# MIDI-Patchbay-Display.net
KiCad netlist of a schematic drawn in EAGLE
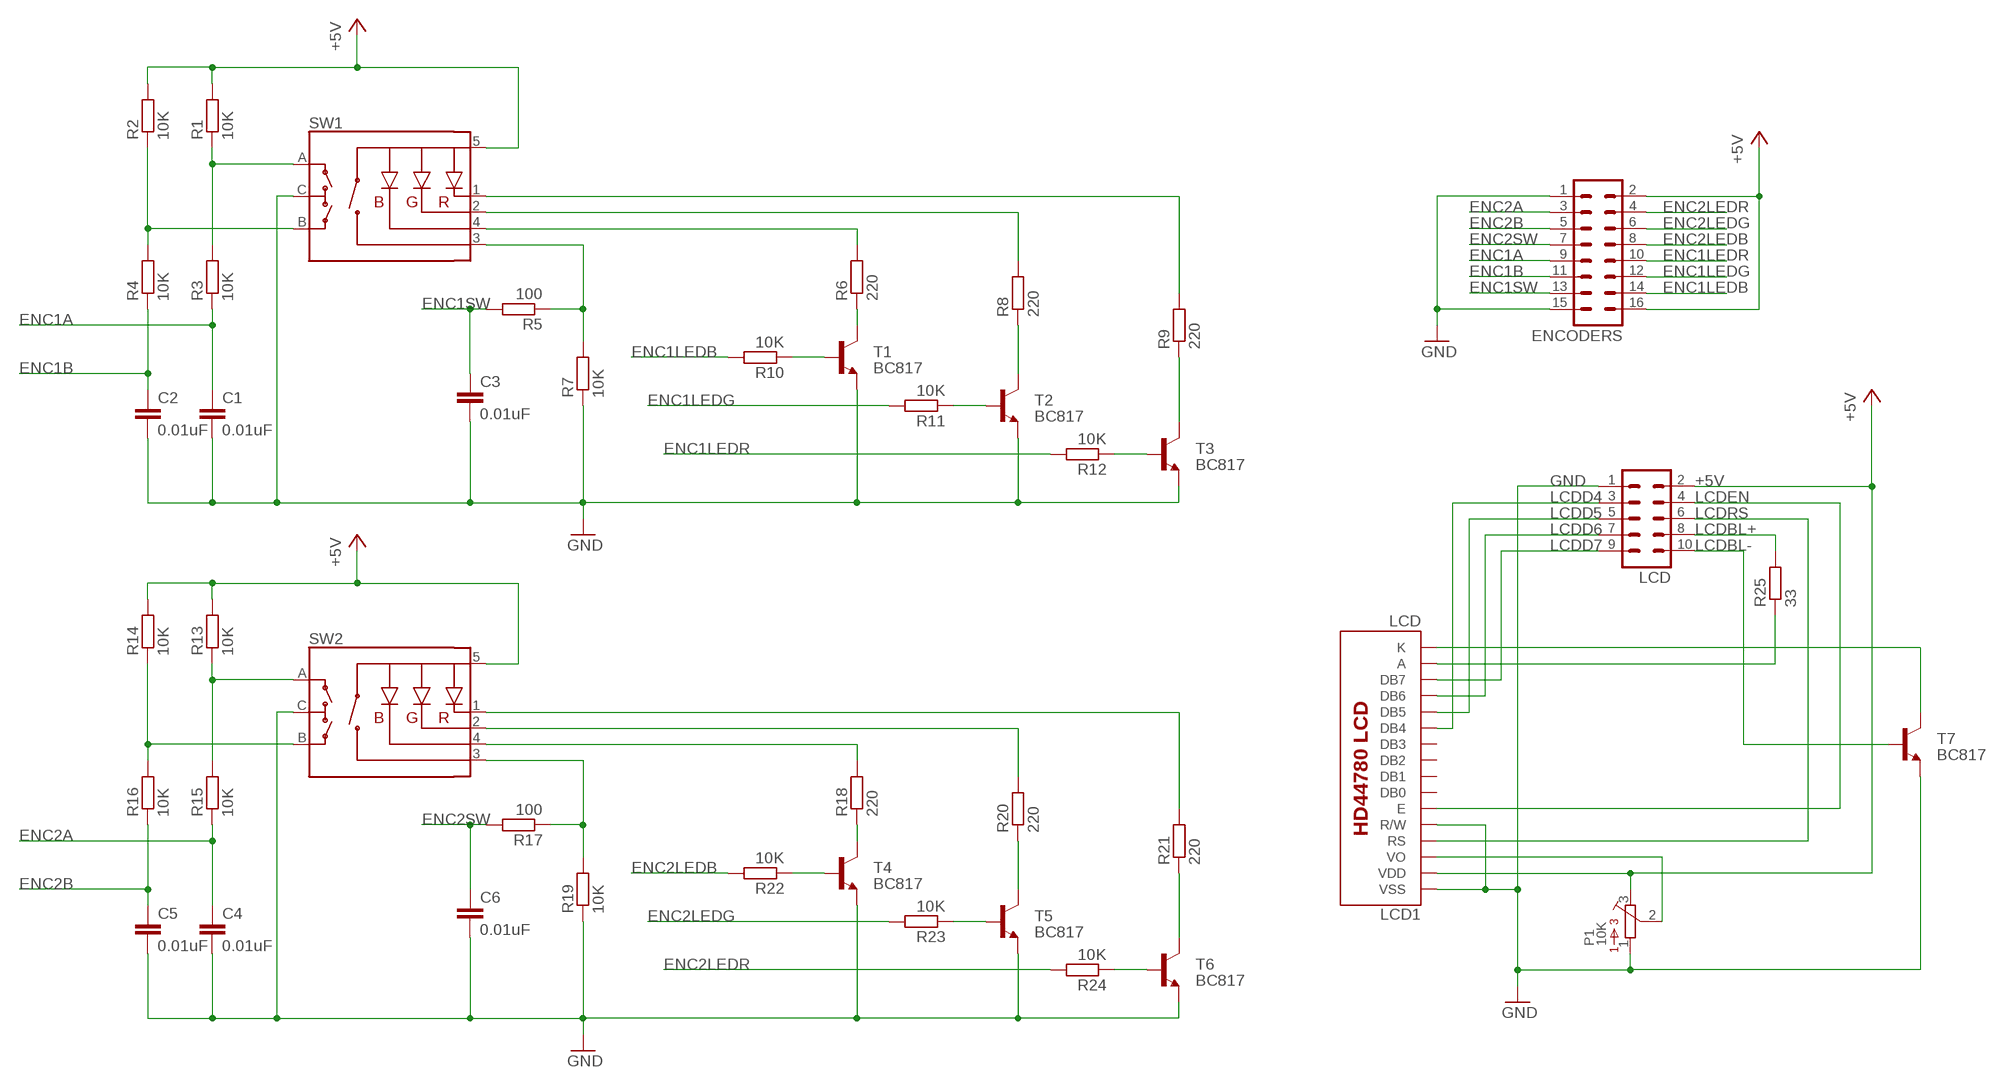
[diagram p0: schematic, sheet 1]

(export (version "E")
  (design (tool "Eeschema 10.0.6"))
  (components
    (comp (ref "C1")
      (value "0.01uF")
      (footprint "eagle-import:0805")
      (libsource (lib "eagle-import") (part "CAPACITOR"))
    )
    (comp (ref "C2")
      (value "0.01uF")
      (footprint "eagle-import:0805")
      (libsource (lib "eagle-import") (part "CAPACITOR"))
    )
    (comp (ref "C3")
      (value "0.01uF")
      (footprint "eagle-import:0805")
      (libsource (lib "eagle-import") (part "CAPACITOR"))
    )
    (comp (ref "C4")
      (value "0.01uF")
      (footprint "eagle-import:0805")
      (libsource (lib "eagle-import") (part "CAPACITOR"))
    )
    (comp (ref "C5")
      (value "0.01uF")
      (footprint "eagle-import:0805")
      (libsource (lib "eagle-import") (part "CAPACITOR"))
    )
    (comp (ref "C6")
      (value "0.01uF")
      (footprint "eagle-import:0805")
      (libsource (lib "eagle-import") (part "CAPACITOR"))
    )
    (comp (ref "ENCODERS")
      (value "ML16")
      (footprint "eagle-import:ML16")
      (libsource (lib "eagle-import") (part "ML16"))
    )
    (comp (ref "LCD")
      (value "ML10")
      (footprint "eagle-import:ML10")
      (libsource (lib "eagle-import") (part "ML10"))
    )
    (comp (ref "LCD1")
      (value "LCD")
      (footprint "eagle-import:LCD-16X2-4HOLES")
      (libsource (lib "eagle-import") (part "LCD-HD4478016X2-4-HOLES4-HOLES"))
    )
    (comp (ref "P1")
      (value "10K")
      (footprint "eagle-import:3386W")
      (libsource (lib "eagle-import") (part "3296W_TRIM_POT"))
    )
    (comp (ref "R1")
      (value "10K")
      (footprint "eagle-import:R0805")
      (libsource (lib "eagle-import") (part "RESISTORR0805"))
    )
    (comp (ref "R2")
      (value "10K")
      (footprint "eagle-import:R0805")
      (libsource (lib "eagle-import") (part "RESISTORR0805"))
    )
    (comp (ref "R3")
      (value "10K")
      (footprint "eagle-import:R0805")
      (libsource (lib "eagle-import") (part "RESISTORR0805"))
    )
    (comp (ref "R4")
      (value "10K")
      (footprint "eagle-import:R0805")
      (libsource (lib "eagle-import") (part "RESISTORR0805"))
    )
    (comp (ref "R5")
      (value "100")
      (footprint "eagle-import:R0805")
      (libsource (lib "eagle-import") (part "RESISTORR0805"))
    )
    (comp (ref "R6")
      (value "220")
      (footprint "eagle-import:R0805")
      (libsource (lib "eagle-import") (part "RESISTORR0805"))
    )
    (comp (ref "R7")
      (value "10K")
      (footprint "eagle-import:R0805")
      (libsource (lib "eagle-import") (part "RESISTORR0805"))
    )
    (comp (ref "R8")
      (value "220")
      (footprint "eagle-import:R0805")
      (libsource (lib "eagle-import") (part "RESISTORR0805"))
    )
    (comp (ref "R9")
      (value "220")
      (footprint "eagle-import:R0805")
      (libsource (lib "eagle-import") (part "RESISTORR0805"))
    )
    (comp (ref "R10")
      (value "10K")
      (footprint "eagle-import:R0805")
      (libsource (lib "eagle-import") (part "RESISTORR0805"))
    )
    (comp (ref "R11")
      (value "10K")
      (footprint "eagle-import:R0805")
      (libsource (lib "eagle-import") (part "RESISTORR0805"))
    )
    (comp (ref "R12")
      (value "10K")
      (footprint "eagle-import:R0805")
      (libsource (lib "eagle-import") (part "RESISTORR0805"))
    )
    (comp (ref "R13")
      (value "10K")
      (footprint "eagle-import:R0805")
      (libsource (lib "eagle-import") (part "RESISTORR0805"))
    )
    (comp (ref "R14")
      (value "10K")
      (footprint "eagle-import:R0805")
      (libsource (lib "eagle-import") (part "RESISTORR0805"))
    )
    (comp (ref "R15")
      (value "10K")
      (footprint "eagle-import:R0805")
      (libsource (lib "eagle-import") (part "RESISTORR0805"))
    )
    (comp (ref "R16")
      (value "10K")
      (footprint "eagle-import:R0805")
      (libsource (lib "eagle-import") (part "RESISTORR0805"))
    )
    (comp (ref "R17")
      (value "100")
      (footprint "eagle-import:R0805")
      (libsource (lib "eagle-import") (part "RESISTORR0805"))
    )
    (comp (ref "R18")
      (value "220")
      (footprint "eagle-import:R0805")
      (libsource (lib "eagle-import") (part "RESISTORR0805"))
    )
    (comp (ref "R19")
      (value "10K")
      (footprint "eagle-import:R0805")
      (libsource (lib "eagle-import") (part "RESISTORR0805"))
    )
    (comp (ref "R20")
      (value "220")
      (footprint "eagle-import:R0805")
      (libsource (lib "eagle-import") (part "RESISTORR0805"))
    )
    (comp (ref "R21")
      (value "220")
      (footprint "eagle-import:R0805")
      (libsource (lib "eagle-import") (part "RESISTORR0805"))
    )
    (comp (ref "R22")
      (value "10K")
      (footprint "eagle-import:R0805")
      (libsource (lib "eagle-import") (part "RESISTORR0805"))
    )
    (comp (ref "R23")
      (value "10K")
      (footprint "eagle-import:R0805")
      (libsource (lib "eagle-import") (part "RESISTORR0805"))
    )
    (comp (ref "R24")
      (value "10K")
      (footprint "eagle-import:R0805")
      (libsource (lib "eagle-import") (part "RESISTORR0805"))
    )
    (comp (ref "R25")
      (value "33")
      (footprint "eagle-import:R0805")
      (libsource (lib "eagle-import") (part "RESISTORR0805"))
    )
    (comp (ref "SW1")
      (value "ENCODER_RGB_CA")
      (footprint "eagle-import:ENCODER_LED_3")
      (libsource (lib "eagle-import") (part "ENCODER_RGB_CA"))
    )
    (comp (ref "SW2")
      (value "ENCODER_RGB_CA")
      (footprint "eagle-import:ENCODER_LED_3")
      (libsource (lib "eagle-import") (part "ENCODER_RGB_CA"))
    )
    (comp (ref "T1")
      (value "BC817")
      (footprint "eagle-import:SOT23")
      (libsource (lib "eagle-import") (part "BC817"))
    )
    (comp (ref "T2")
      (value "BC817")
      (footprint "eagle-import:SOT23")
      (libsource (lib "eagle-import") (part "BC817"))
    )
    (comp (ref "T3")
      (value "BC817")
      (footprint "eagle-import:SOT23")
      (libsource (lib "eagle-import") (part "BC817"))
    )
    (comp (ref "T4")
      (value "BC817")
      (footprint "eagle-import:SOT23")
      (libsource (lib "eagle-import") (part "BC817"))
    )
    (comp (ref "T5")
      (value "BC817")
      (footprint "eagle-import:SOT23")
      (libsource (lib "eagle-import") (part "BC817"))
    )
    (comp (ref "T6")
      (value "BC817")
      (footprint "eagle-import:SOT23")
      (libsource (lib "eagle-import") (part "BC817"))
    )
    (comp (ref "T7")
      (value "BC817")
      (footprint "eagle-import:SOT23")
      (libsource (lib "eagle-import") (part "BC817"))
    )
  )
  (nets
    (net (code "1") (name "+5V") (class "Default")
      (node (ref "ENCODERS") (pin "16") (pinfunction "16_16") (pintype "passive"))
      (node (ref "ENCODERS") (pin "2") (pinfunction "2_2") (pintype "passive"))
      (node (ref "LCD") (pin "2") (pinfunction "2_2") (pintype "passive"))
      (node (ref "LCD1") (pin "2") (pinfunction "VDD_2") (pintype "power_in"))
      (node (ref "P1") (pin "3") (pinfunction "3_3") (pintype "passive"))
      (node (ref "R1") (pin "2") (pinfunction "2_2") (pintype "passive"))
      (node (ref "R13") (pin "2") (pinfunction "2_2") (pintype "passive"))
      (node (ref "R14") (pin "2") (pinfunction "2_2") (pintype "passive"))
      (node (ref "R2") (pin "2") (pinfunction "2_2") (pintype "passive"))
      (node (ref "SW1") (pin "5") (pinfunction "+_5") (pintype "passive"))
      (node (ref "SW2") (pin "5") (pinfunction "+_5") (pintype "passive"))
    )
    (net (code "2") (name "/ENC1A") (class "Default")
      (node (ref "C1") (pin "1") (pinfunction "1_1") (pintype "passive"))
      (node (ref "ENCODERS") (pin "9") (pinfunction "9_9") (pintype "passive"))
      (node (ref "R3") (pin "1") (pinfunction "1_1") (pintype "passive"))
    )
    (net (code "3") (name "/ENC1B") (class "Default")
      (node (ref "C2") (pin "1") (pinfunction "1_1") (pintype "passive"))
      (node (ref "ENCODERS") (pin "11") (pinfunction "11_11") (pintype "passive"))
      (node (ref "R4") (pin "1") (pinfunction "1_1") (pintype "passive"))
    )
    (net (code "4") (name "/ENC1LEDB") (class "Default")
      (node (ref "ENCODERS") (pin "14") (pinfunction "14_14") (pintype "passive"))
      (node (ref "R10") (pin "2") (pinfunction "2_2") (pintype "passive"))
    )
    (net (code "5") (name "/ENC1LEDG") (class "Default")
      (node (ref "ENCODERS") (pin "12") (pinfunction "12_12") (pintype "passive"))
      (node (ref "R11") (pin "2") (pinfunction "2_2") (pintype "passive"))
    )
    (net (code "6") (name "/ENC1LEDR") (class "Default")
      (node (ref "ENCODERS") (pin "10") (pinfunction "10_10") (pintype "passive"))
      (node (ref "R12") (pin "2") (pinfunction "2_2") (pintype "passive"))
    )
    (net (code "7") (name "/ENC1SW") (class "Default")
      (node (ref "C3") (pin "1") (pinfunction "1_1") (pintype "passive"))
      (node (ref "ENCODERS") (pin "13") (pinfunction "13_13") (pintype "passive"))
      (node (ref "R5") (pin "2") (pinfunction "2_2") (pintype "passive"))
    )
    (net (code "8") (name "/ENC2A") (class "Default")
      (node (ref "C4") (pin "1") (pinfunction "1_1") (pintype "passive"))
      (node (ref "ENCODERS") (pin "3") (pinfunction "3_3") (pintype "passive"))
      (node (ref "R15") (pin "1") (pinfunction "1_1") (pintype "passive"))
    )
    (net (code "9") (name "/ENC2B") (class "Default")
      (node (ref "C5") (pin "1") (pinfunction "1_1") (pintype "passive"))
      (node (ref "ENCODERS") (pin "5") (pinfunction "5_5") (pintype "passive"))
      (node (ref "R16") (pin "1") (pinfunction "1_1") (pintype "passive"))
    )
    (net (code "10") (name "/ENC2LEDB") (class "Default")
      (node (ref "ENCODERS") (pin "8") (pinfunction "8_8") (pintype "passive"))
      (node (ref "R22") (pin "2") (pinfunction "2_2") (pintype "passive"))
    )
    (net (code "11") (name "/ENC2LEDG") (class "Default")
      (node (ref "ENCODERS") (pin "6") (pinfunction "6_6") (pintype "passive"))
      (node (ref "R23") (pin "2") (pinfunction "2_2") (pintype "passive"))
    )
    (net (code "12") (name "/ENC2LEDR") (class "Default")
      (node (ref "ENCODERS") (pin "4") (pinfunction "4_4") (pintype "passive"))
      (node (ref "R24") (pin "2") (pinfunction "2_2") (pintype "passive"))
    )
    (net (code "13") (name "/ENC2SW") (class "Default")
      (node (ref "C6") (pin "1") (pinfunction "1_1") (pintype "passive"))
      (node (ref "ENCODERS") (pin "7") (pinfunction "7_7") (pintype "passive"))
      (node (ref "R17") (pin "2") (pinfunction "2_2") (pintype "passive"))
    )
    (net (code "14") (name "/LCDBL+") (class "Default")
      (node (ref "LCD") (pin "8") (pinfunction "8_8") (pintype "passive"))
      (node (ref "R25") (pin "2") (pinfunction "2_2") (pintype "passive"))
    )
    (net (code "15") (name "/LCDBL-") (class "Default")
      (node (ref "LCD") (pin "10") (pinfunction "10_10") (pintype "passive"))
      (node (ref "T7") (pin "1") (pinfunction "B_1") (pintype "passive"))
    )
    (net (code "16") (name "/LCDD4") (class "Default")
      (node (ref "LCD") (pin "3") (pinfunction "3_3") (pintype "passive"))
      (node (ref "LCD1") (pin "11") (pinfunction "DB4_11") (pintype "bidirectional"))
    )
    (net (code "17") (name "/LCDD5") (class "Default")
      (node (ref "LCD") (pin "5") (pinfunction "5_5") (pintype "passive"))
      (node (ref "LCD1") (pin "12") (pinfunction "DB5_12") (pintype "bidirectional"))
    )
    (net (code "18") (name "/LCDD6") (class "Default")
      (node (ref "LCD") (pin "7") (pinfunction "7_7") (pintype "passive"))
      (node (ref "LCD1") (pin "13") (pinfunction "DB6_13") (pintype "bidirectional"))
    )
    (net (code "19") (name "/LCDD7") (class "Default")
      (node (ref "LCD") (pin "9") (pinfunction "9_9") (pintype "passive"))
      (node (ref "LCD1") (pin "14") (pinfunction "DB7_14") (pintype "bidirectional"))
    )
    (net (code "20") (name "/LCDEN") (class "Default")
      (node (ref "LCD") (pin "4") (pinfunction "4_4") (pintype "passive"))
      (node (ref "LCD1") (pin "6") (pinfunction "E_6") (pintype "input"))
    )
    (net (code "21") (name "/LCDRS") (class "Default")
      (node (ref "LCD") (pin "6") (pinfunction "6_6") (pintype "passive"))
      (node (ref "LCD1") (pin "4") (pinfunction "RS_4") (pintype "input"))
    )
    (net (code "22") (name "GND") (class "Default")
      (node (ref "C1") (pin "2") (pinfunction "2_2") (pintype "passive"))
      (node (ref "C2") (pin "2") (pinfunction "2_2") (pintype "passive"))
      (node (ref "C3") (pin "2") (pinfunction "2_2") (pintype "passive"))
      (node (ref "C4") (pin "2") (pinfunction "2_2") (pintype "passive"))
      (node (ref "C5") (pin "2") (pinfunction "2_2") (pintype "passive"))
      (node (ref "C6") (pin "2") (pinfunction "2_2") (pintype "passive"))
      (node (ref "ENCODERS") (pin "1") (pinfunction "1_1") (pintype "passive"))
      (node (ref "ENCODERS") (pin "15") (pinfunction "15_15") (pintype "passive"))
      (node (ref "LCD") (pin "1") (pinfunction "1_1") (pintype "passive"))
      (node (ref "LCD1") (pin "1") (pinfunction "VSS_1") (pintype "power_in"))
      (node (ref "LCD1") (pin "5") (pinfunction "R/W_5") (pintype "input"))
      (node (ref "P1") (pin "1") (pinfunction "1_1") (pintype "passive"))
      (node (ref "R19") (pin "1") (pinfunction "1_1") (pintype "passive"))
      (node (ref "R7") (pin "1") (pinfunction "1_1") (pintype "passive"))
      (node (ref "SW1") (pin "C") (pinfunction "C_C") (pintype "bidirectional"))
      (node (ref "SW2") (pin "C") (pinfunction "C_C") (pintype "bidirectional"))
      (node (ref "T1") (pin "2") (pinfunction "E_2") (pintype "passive"))
      (node (ref "T2") (pin "2") (pinfunction "E_2") (pintype "passive"))
      (node (ref "T3") (pin "2") (pinfunction "E_2") (pintype "passive"))
      (node (ref "T4") (pin "2") (pinfunction "E_2") (pintype "passive"))
      (node (ref "T5") (pin "2") (pinfunction "E_2") (pintype "passive"))
      (node (ref "T6") (pin "2") (pinfunction "E_2") (pintype "passive"))
      (node (ref "T7") (pin "2") (pinfunction "E_2") (pintype "passive"))
    )
    (net (code "23") (name "Net-(LCD1-A)") (class "Default")
      (node (ref "LCD1") (pin "15") (pinfunction "A_15") (pintype "power_in"))
      (node (ref "R25") (pin "1") (pinfunction "1_1") (pintype "passive"))
    )
    (net (code "24") (name "Net-(LCD1-K)") (class "Default")
      (node (ref "LCD1") (pin "16") (pinfunction "K_16") (pintype "power_in"))
      (node (ref "T7") (pin "3") (pinfunction "C_3") (pintype "passive"))
    )
    (net (code "25") (name "Net-(LCD1-VO)") (class "Default")
      (node (ref "LCD1") (pin "3") (pinfunction "VO_3") (pintype "bidirectional"))
      (node (ref "P1") (pin "2") (pinfunction "2_2") (pintype "passive"))
    )
    (net (code "26") (name "Net-(R1-Pad1)") (class "Default")
      (node (ref "R1") (pin "1") (pinfunction "1_1") (pintype "passive"))
      (node (ref "R3") (pin "2") (pinfunction "2_2") (pintype "passive"))
      (node (ref "SW1") (pin "A") (pinfunction "A_A") (pintype "bidirectional"))
    )
    (net (code "27") (name "Net-(R2-Pad1)") (class "Default")
      (node (ref "R2") (pin "1") (pinfunction "1_1") (pintype "passive"))
      (node (ref "R4") (pin "2") (pinfunction "2_2") (pintype "passive"))
      (node (ref "SW1") (pin "B") (pinfunction "B_B") (pintype "bidirectional"))
    )
    (net (code "28") (name "Net-(R13-Pad1)") (class "Default")
      (node (ref "R13") (pin "1") (pinfunction "1_1") (pintype "passive"))
      (node (ref "R15") (pin "2") (pinfunction "2_2") (pintype "passive"))
      (node (ref "SW2") (pin "A") (pinfunction "A_A") (pintype "bidirectional"))
    )
    (net (code "29") (name "Net-(R14-Pad1)") (class "Default")
      (node (ref "R14") (pin "1") (pinfunction "1_1") (pintype "passive"))
      (node (ref "R16") (pin "2") (pinfunction "2_2") (pintype "passive"))
      (node (ref "SW2") (pin "B") (pinfunction "B_B") (pintype "bidirectional"))
    )
    (net (code "30") (name "Net-(SW1--B)") (class "Default")
      (node (ref "R6") (pin "2") (pinfunction "2_2") (pintype "passive"))
      (node (ref "SW1") (pin "4") (pinfunction "-B_4") (pintype "passive"))
    )
    (net (code "31") (name "Net-(SW1--G)") (class "Default")
      (node (ref "R8") (pin "2") (pinfunction "2_2") (pintype "passive"))
      (node (ref "SW1") (pin "2") (pinfunction "-G_2") (pintype "passive"))
    )
    (net (code "32") (name "Net-(SW1--R)") (class "Default")
      (node (ref "R9") (pin "2") (pinfunction "2_2") (pintype "passive"))
      (node (ref "SW1") (pin "1") (pinfunction "-R_1") (pintype "passive"))
    )
    (net (code "33") (name "Net-(SW1-SW)") (class "Default")
      (node (ref "R5") (pin "1") (pinfunction "1_1") (pintype "passive"))
      (node (ref "R7") (pin "2") (pinfunction "2_2") (pintype "passive"))
      (node (ref "SW1") (pin "3") (pinfunction "SW_3") (pintype "passive"))
    )
    (net (code "34") (name "Net-(SW2--B)") (class "Default")
      (node (ref "R18") (pin "2") (pinfunction "2_2") (pintype "passive"))
      (node (ref "SW2") (pin "4") (pinfunction "-B_4") (pintype "passive"))
    )
    (net (code "35") (name "Net-(SW2--G)") (class "Default")
      (node (ref "R20") (pin "2") (pinfunction "2_2") (pintype "passive"))
      (node (ref "SW2") (pin "2") (pinfunction "-G_2") (pintype "passive"))
    )
    (net (code "36") (name "Net-(SW2--R)") (class "Default")
      (node (ref "R21") (pin "2") (pinfunction "2_2") (pintype "passive"))
      (node (ref "SW2") (pin "1") (pinfunction "-R_1") (pintype "passive"))
    )
    (net (code "37") (name "Net-(SW2-SW)") (class "Default")
      (node (ref "R17") (pin "1") (pinfunction "1_1") (pintype "passive"))
      (node (ref "R19") (pin "2") (pinfunction "2_2") (pintype "passive"))
      (node (ref "SW2") (pin "3") (pinfunction "SW_3") (pintype "passive"))
    )
    (net (code "38") (name "Net-(T1-B)") (class "Default")
      (node (ref "R10") (pin "1") (pinfunction "1_1") (pintype "passive"))
      (node (ref "T1") (pin "1") (pinfunction "B_1") (pintype "passive"))
    )
    (net (code "39") (name "Net-(T1-C)") (class "Default")
      (node (ref "R6") (pin "1") (pinfunction "1_1") (pintype "passive"))
      (node (ref "T1") (pin "3") (pinfunction "C_3") (pintype "passive"))
    )
    (net (code "40") (name "Net-(T2-B)") (class "Default")
      (node (ref "R11") (pin "1") (pinfunction "1_1") (pintype "passive"))
      (node (ref "T2") (pin "1") (pinfunction "B_1") (pintype "passive"))
    )
    (net (code "41") (name "Net-(T2-C)") (class "Default")
      (node (ref "R8") (pin "1") (pinfunction "1_1") (pintype "passive"))
      (node (ref "T2") (pin "3") (pinfunction "C_3") (pintype "passive"))
    )
    (net (code "42") (name "Net-(T3-B)") (class "Default")
      (node (ref "R12") (pin "1") (pinfunction "1_1") (pintype "passive"))
      (node (ref "T3") (pin "1") (pinfunction "B_1") (pintype "passive"))
    )
    (net (code "43") (name "Net-(T3-C)") (class "Default")
      (node (ref "R9") (pin "1") (pinfunction "1_1") (pintype "passive"))
      (node (ref "T3") (pin "3") (pinfunction "C_3") (pintype "passive"))
    )
    (net (code "44") (name "Net-(T4-B)") (class "Default")
      (node (ref "R22") (pin "1") (pinfunction "1_1") (pintype "passive"))
      (node (ref "T4") (pin "1") (pinfunction "B_1") (pintype "passive"))
    )
    (net (code "45") (name "Net-(T4-C)") (class "Default")
      (node (ref "R18") (pin "1") (pinfunction "1_1") (pintype "passive"))
      (node (ref "T4") (pin "3") (pinfunction "C_3") (pintype "passive"))
    )
    (net (code "46") (name "Net-(T5-B)") (class "Default")
      (node (ref "R23") (pin "1") (pinfunction "1_1") (pintype "passive"))
      (node (ref "T5") (pin "1") (pinfunction "B_1") (pintype "passive"))
    )
    (net (code "47") (name "Net-(T5-C)") (class "Default")
      (node (ref "R20") (pin "1") (pinfunction "1_1") (pintype "passive"))
      (node (ref "T5") (pin "3") (pinfunction "C_3") (pintype "passive"))
    )
    (net (code "48") (name "Net-(T6-B)") (class "Default")
      (node (ref "R24") (pin "1") (pinfunction "1_1") (pintype "passive"))
      (node (ref "T6") (pin "1") (pinfunction "B_1") (pintype "passive"))
    )
    (net (code "49") (name "Net-(T6-C)") (class "Default")
      (node (ref "R21") (pin "1") (pinfunction "1_1") (pintype "passive"))
      (node (ref "T6") (pin "3") (pinfunction "C_3") (pintype "passive"))
    )
    (net (code "50") (name "unconnected-(LCD1-DB0-Pad7)") (class "Default")
      (node (ref "LCD1") (pin "7") (pinfunction "DB0_7") (pintype "bidirectional"))
    )
    (net (code "51") (name "unconnected-(LCD1-DB1-Pad8)") (class "Default")
      (node (ref "LCD1") (pin "8") (pinfunction "DB1_8") (pintype "bidirectional"))
    )
    (net (code "52") (name "unconnected-(LCD1-DB2-Pad9)") (class "Default")
      (node (ref "LCD1") (pin "9") (pinfunction "DB2_9") (pintype "bidirectional"))
    )
    (net (code "53") (name "unconnected-(LCD1-DB3-Pad10)") (class "Default")
      (node (ref "LCD1") (pin "10") (pinfunction "DB3_10") (pintype "bidirectional"))
    )
  )
)
